# Sheet1.net
KiCad netlist of a schematic drawn in Altium Designer
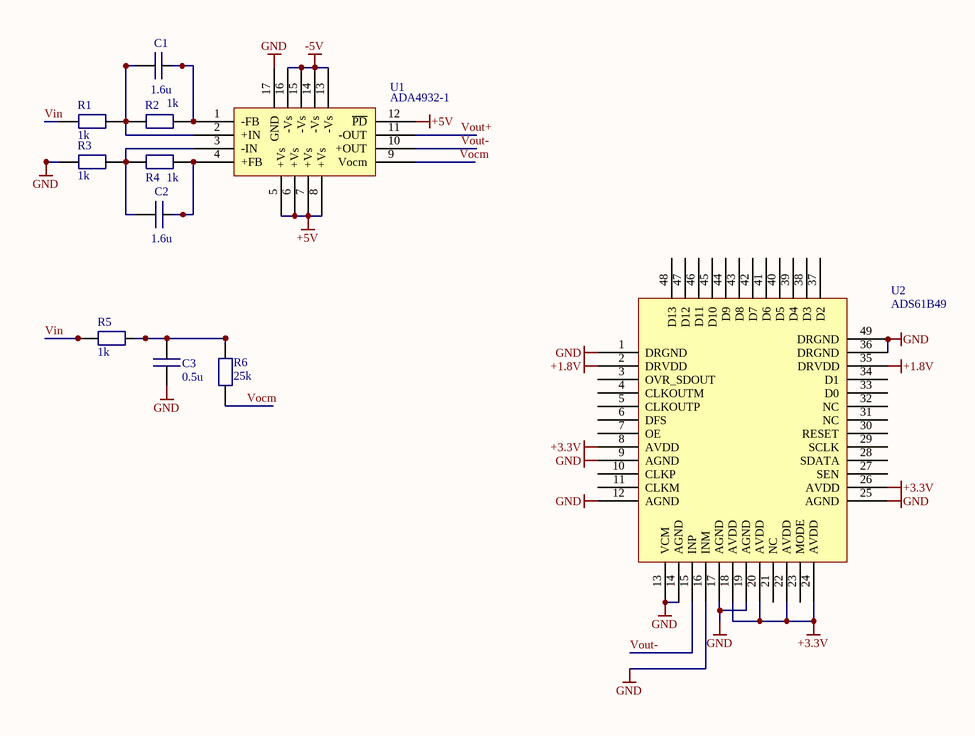
[diagram p0: Sheet1.SchDoc]

(export (version "E")
  (design (tool "Eeschema 10.0.6"))
  (components
    (comp (ref "C1") (value "1.6u") (footprint "1608[0603]") (libsource (lib "Schlib1") (part "Cap")))
    (comp (ref "C2") (value "1.6u") (footprint "1608[0603]") (libsource (lib "Schlib1") (part "Cap")))
    (comp (ref "C3") (value "0.5u") (footprint "1608[0603]") (libsource (lib "Schlib1") (part "Cap")))
    (comp (ref "R1") (value "1k") (footprint "1608[0603]") (libsource (lib "Schlib1") (part "Res")))
    (comp (ref "R2") (value "1k") (footprint "1608[0603]") (libsource (lib "Schlib1") (part "Res")))
    (comp (ref "R3") (value "1k") (footprint "1608[0603]") (libsource (lib "Schlib1") (part "Res")))
    (comp (ref "R4") (value "1k") (footprint "1608[0603]") (libsource (lib "Schlib1") (part "Res")))
    (comp (ref "R5") (value "1k") (footprint "1608[0603]") (libsource (lib "Schlib1") (part "Res")))
    (comp (ref "R6") (value "25k") (footprint "1608[0603]") (libsource (lib "Schlib1") (part "Res")))
    (comp (ref "U1")
      (value "ADA4932-1")
      (footprint "QFN50P300X300X100_HS-17N")
      (libsource (lib "Schlib1") (part "ADA4932-1"))
    )
    (comp (ref "U2")
      (value "ADS61B49")
      (footprint "QFN50P780X780X100_HS-49N")
      (libsource (lib "Schlib1") (part "ADS61B49"))
    )
  )
  (nets
    (net (code "1") (name "+1.8V") (class "Default")
      (node (ref "U2") (pin "2") (pinfunction "DRVDD_2") (pintype "passive"))
      (node (ref "U2") (pin "35") (pinfunction "DRVDD_35") (pintype "passive"))
    )
    (net (code "2") (name "+3.3V") (class "Default")
      (node (ref "U2") (pin "18") (pinfunction "AVDD_18") (pintype "passive"))
      (node (ref "U2") (pin "20") (pinfunction "AVDD_20") (pintype "passive"))
      (node (ref "U2") (pin "22") (pinfunction "AVDD_22") (pintype "passive"))
      (node (ref "U2") (pin "24") (pinfunction "AVDD_24") (pintype "passive"))
      (node (ref "U2") (pin "26") (pinfunction "AVDD_26") (pintype "passive"))
      (node (ref "U2") (pin "8") (pinfunction "AVDD_8") (pintype "passive"))
    )
    (net (code "3") (name "+5V") (class "Default")
      (node (ref "U1") (pin "12") (pinfunction "~{PD}_12") (pintype "passive"))
      (node (ref "U1") (pin "5") (pinfunction "+Vs_5") (pintype "passive"))
      (node (ref "U1") (pin "6") (pinfunction "+Vs_6") (pintype "passive"))
      (node (ref "U1") (pin "7") (pinfunction "+Vs_7") (pintype "passive"))
      (node (ref "U1") (pin "8") (pinfunction "+Vs_8") (pintype "passive"))
    )
    (net (code "4") (name "-5V") (class "Default")
      (node (ref "U1") (pin "13") (pinfunction "-Vs_13") (pintype "passive"))
      (node (ref "U1") (pin "14") (pinfunction "-Vs_14") (pintype "passive"))
      (node (ref "U1") (pin "15") (pinfunction "-Vs_15") (pintype "passive"))
      (node (ref "U1") (pin "16") (pinfunction "-Vs_16") (pintype "passive"))
    )
    (net (code "5") (name "/Vin") (class "Default")
      (node (ref "R1") (pin "1") (pintype "passive"))
      (node (ref "R5") (pin "1") (pintype "passive"))
    )
    (net (code "6") (name "/Vocm") (class "Default")
      (node (ref "R6") (pin "1") (pintype "passive"))
      (node (ref "U1") (pin "9") (pinfunction "Vocm_9") (pintype "passive"))
    )
    (net (code "7") (name "/Vout+") (class "Default")
      (node (ref "U1") (pin "11") (pinfunction "-OUT_11") (pintype "passive"))
    )
    (net (code "8") (name "/Vout-") (class "Default")
      (node (ref "U1") (pin "10") (pinfunction "+OUT_10") (pintype "passive"))
      (node (ref "U2") (pin "15") (pinfunction "INP_15") (pintype "passive"))
    )
    (net (code "9") (name "GND") (class "Default")
      (node (ref "C3") (pin "1") (pintype "passive"))
      (node (ref "R3") (pin "1") (pintype "passive"))
      (node (ref "U1") (pin "17") (pinfunction "GND_17") (pintype "passive"))
      (node (ref "U2") (pin "1") (pinfunction "DRGND_1") (pintype "passive"))
      (node (ref "U2") (pin "12") (pinfunction "AGND_12") (pintype "passive"))
      (node (ref "U2") (pin "13") (pinfunction "VCM_13") (pintype "passive"))
      (node (ref "U2") (pin "14") (pinfunction "AGND_14") (pintype "passive"))
      (node (ref "U2") (pin "16") (pinfunction "INM_16") (pintype "passive"))
      (node (ref "U2") (pin "17") (pinfunction "AGND_17") (pintype "passive"))
      (node (ref "U2") (pin "19") (pinfunction "AGND_19") (pintype "passive"))
      (node (ref "U2") (pin "25") (pinfunction "AGND_25") (pintype "passive"))
      (node (ref "U2") (pin "36") (pinfunction "DRGND_36") (pintype "passive"))
      (node (ref "U2") (pin "49") (pinfunction "DRGND_49") (pintype "passive"))
      (node (ref "U2") (pin "9") (pinfunction "AGND_9") (pintype "passive"))
    )
    (net (code "10") (name "Net-(C3-Pad2)") (class "Default")
      (node (ref "C3") (pin "2") (pintype "passive"))
      (node (ref "R5") (pin "2") (pintype "passive"))
      (node (ref "R6") (pin "2") (pintype "passive"))
    )
    (net (code "11") (name "Net-(U1-+FB)") (class "Default")
      (node (ref "C2") (pin "1") (pintype "passive"))
      (node (ref "R4") (pin "2") (pintype "passive"))
      (node (ref "U1") (pin "4") (pinfunction "+FB_4") (pintype "passive"))
    )
    (net (code "12") (name "Net-(U1-+IN)") (class "Default")
      (node (ref "C1") (pin "2") (pintype "passive"))
      (node (ref "R1") (pin "2") (pintype "passive"))
      (node (ref "R2") (pin "1") (pintype "passive"))
      (node (ref "U1") (pin "2") (pinfunction "+IN_2") (pintype "passive"))
    )
    (net (code "13") (name "Net-(U1--FB)") (class "Default")
      (node (ref "C1") (pin "1") (pintype "passive"))
      (node (ref "R2") (pin "2") (pintype "passive"))
      (node (ref "U1") (pin "1") (pinfunction "-FB_1") (pintype "passive"))
    )
    (net (code "14") (name "Net-(U1--IN)") (class "Default")
      (node (ref "C2") (pin "2") (pintype "passive"))
      (node (ref "R3") (pin "2") (pintype "passive"))
      (node (ref "R4") (pin "1") (pintype "passive"))
      (node (ref "U1") (pin "3") (pinfunction "-IN_3") (pintype "passive"))
    )
    (net (code "15") (name "unconnected-(U2-CLKM-Pad11)") (class "Default")
      (node (ref "U2") (pin "11") (pinfunction "CLKM_11") (pintype "passive"))
    )
    (net (code "16") (name "unconnected-(U2-CLKOUTM-Pad4)") (class "Default")
      (node (ref "U2") (pin "4") (pinfunction "CLKOUTM_4") (pintype "passive"))
    )
    (net (code "17") (name "unconnected-(U2-CLKOUTP-Pad5)") (class "Default")
      (node (ref "U2") (pin "5") (pinfunction "CLKOUTP_5") (pintype "passive"))
    )
    (net (code "18") (name "unconnected-(U2-CLKP-Pad10)") (class "Default")
      (node (ref "U2") (pin "10") (pinfunction "CLKP_10") (pintype "passive"))
    )
    (net (code "19") (name "unconnected-(U2-D0-Pad33)") (class "Default")
      (node (ref "U2") (pin "33") (pinfunction "D0_33") (pintype "passive"))
    )
    (net (code "20") (name "unconnected-(U2-D1-Pad34)") (class "Default")
      (node (ref "U2") (pin "34") (pinfunction "D1_34") (pintype "passive"))
    )
    (net (code "21") (name "unconnected-(U2-D2-Pad37)") (class "Default")
      (node (ref "U2") (pin "37") (pinfunction "D2_37") (pintype "passive"))
    )
    (net (code "22") (name "unconnected-(U2-D3-Pad38)") (class "Default")
      (node (ref "U2") (pin "38") (pinfunction "D3_38") (pintype "passive"))
    )
    (net (code "23") (name "unconnected-(U2-D4-Pad39)") (class "Default")
      (node (ref "U2") (pin "39") (pinfunction "D4_39") (pintype "passive"))
    )
    (net (code "24") (name "unconnected-(U2-D5-Pad40)") (class "Default")
      (node (ref "U2") (pin "40") (pinfunction "D5_40") (pintype "passive"))
    )
    (net (code "25") (name "unconnected-(U2-D6-Pad41)") (class "Default")
      (node (ref "U2") (pin "41") (pinfunction "D6_41") (pintype "passive"))
    )
    (net (code "26") (name "unconnected-(U2-D7-Pad42)") (class "Default")
      (node (ref "U2") (pin "42") (pinfunction "D7_42") (pintype "passive"))
    )
    (net (code "27") (name "unconnected-(U2-D8-Pad43)") (class "Default")
      (node (ref "U2") (pin "43") (pinfunction "D8_43") (pintype "passive"))
    )
    (net (code "28") (name "unconnected-(U2-D9-Pad44)") (class "Default")
      (node (ref "U2") (pin "44") (pinfunction "D9_44") (pintype "passive"))
    )
    (net (code "29") (name "unconnected-(U2-D10-Pad45)") (class "Default")
      (node (ref "U2") (pin "45") (pinfunction "D10_45") (pintype "passive"))
    )
    (net (code "30") (name "unconnected-(U2-D11-Pad46)") (class "Default")
      (node (ref "U2") (pin "46") (pinfunction "D11_46") (pintype "passive"))
    )
    (net (code "31") (name "unconnected-(U2-D12-Pad47)") (class "Default")
      (node (ref "U2") (pin "47") (pinfunction "D12_47") (pintype "passive"))
    )
    (net (code "32") (name "unconnected-(U2-D13-Pad48)") (class "Default")
      (node (ref "U2") (pin "48") (pinfunction "D13_48") (pintype "passive"))
    )
    (net (code "33") (name "unconnected-(U2-DFS-Pad6)") (class "Default")
      (node (ref "U2") (pin "6") (pinfunction "DFS_6") (pintype "passive"))
    )
    (net (code "34") (name "unconnected-(U2-MODE-Pad23)") (class "Default")
      (node (ref "U2") (pin "23") (pinfunction "MODE_23") (pintype "passive"))
    )
    (net (code "35") (name "unconnected-(U2-NC-Pad21)") (class "Default")
      (node (ref "U2") (pin "21") (pinfunction "NC_21") (pintype "passive"))
    )
    (net (code "36") (name "unconnected-(U2-NC-Pad31)") (class "Default")
      (node (ref "U2") (pin "31") (pinfunction "NC_31") (pintype "passive"))
    )
    (net (code "37") (name "unconnected-(U2-NC-Pad32)") (class "Default")
      (node (ref "U2") (pin "32") (pinfunction "NC_32") (pintype "passive"))
    )
    (net (code "38") (name "unconnected-(U2-OE-Pad7)") (class "Default")
      (node (ref "U2") (pin "7") (pinfunction "OE_7") (pintype "passive"))
    )
    (net (code "39") (name "unconnected-(U2-OVR_SDOUT-Pad3)") (class "Default")
      (node (ref "U2") (pin "3") (pinfunction "OVR_SDOUT_3") (pintype "passive"))
    )
    (net (code "40") (name "unconnected-(U2-RESET-Pad30)") (class "Default")
      (node (ref "U2") (pin "30") (pinfunction "RESET_30") (pintype "passive"))
    )
    (net (code "41") (name "unconnected-(U2-SCLK-Pad29)") (class "Default")
      (node (ref "U2") (pin "29") (pinfunction "SCLK_29") (pintype "passive"))
    )
    (net (code "42") (name "unconnected-(U2-SDATA-Pad28)") (class "Default")
      (node (ref "U2") (pin "28") (pinfunction "SDATA_28") (pintype "passive"))
    )
    (net (code "43") (name "unconnected-(U2-SEN-Pad27)") (class "Default")
      (node (ref "U2") (pin "27") (pinfunction "SEN_27") (pintype "passive"))
    )
  )
)
